# nunchuck_v0_4.net
KiCad netlist of a schematic drawn in EAGLE
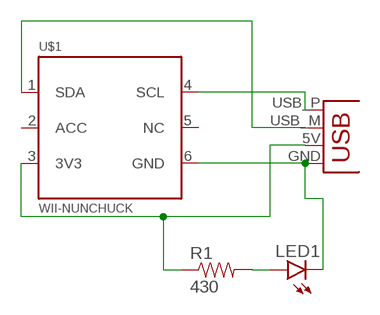
[diagram p0: schematic, sheet 1]

(export (version "E")
  (design (tool "Eeschema 10.0.6"))
  (components
    (comp (ref "JP1")
      (value "USBPCB")
      (footprint "eagle-import:USB-A-PCB")
      (libsource (lib "eagle-import") (part "USBPCB"))
    )
    (comp (ref "LED1")
      (value "LED0603")
      (footprint "eagle-import:LED-0603")
      (libsource (lib "eagle-import") (part "LED0603"))
    )
    (comp (ref "R1")
      (value "430")
      (footprint "eagle-import:0603-RES")
      (libsource (lib "eagle-import") (part "RESISTOR0603"))
    )
    (comp (ref "U$1")
      (value "WII-NUNCHUCK")
      (footprint "eagle-import:WII_6PIN")
      (libsource (lib "eagle-import") (part "WII-NUNCHUCK"))
    )
  )
  (nets
    (net (code "1") (name "Net-(JP1-D+)") (class "Default")
      (node (ref "JP1") (pin "USB_P") (pinfunction "D+_USB_P") (pintype "bidirectional"))
      (node (ref "U$1") (pin "4") (pinfunction "SCL_4") (pintype "bidirectional"))
    )
    (net (code "2") (name "Net-(JP1-D-)") (class "Default")
      (node (ref "JP1") (pin "USB_M") (pinfunction "D-_USB_M") (pintype "bidirectional"))
      (node (ref "U$1") (pin "1") (pinfunction "SDA_1") (pintype "bidirectional"))
    )
    (net (code "3") (name "Net-(JP1-VBUS)") (class "Default")
      (node (ref "JP1") (pin "5V") (pinfunction "VBUS_5V") (pintype "bidirectional"))
      (node (ref "R1") (pin "1") (pinfunction "1_1") (pintype "passive"))
      (node (ref "U$1") (pin "3") (pinfunction "3V3_3") (pintype "power_in"))
    )
    (net (code "4") (name "Net-(LED1-PadA)") (class "Default")
      (node (ref "LED1") (pin "A") (pinfunction "A_A") (pintype "passive"))
      (node (ref "R1") (pin "2") (pinfunction "2_2") (pintype "passive"))
    )
    (net (code "5") (name "Net-(U$1-GND)") (class "Default")
      (node (ref "JP1") (pin "GND") (pinfunction "GND_GND") (pintype "bidirectional"))
      (node (ref "LED1") (pin "C") (pinfunction "C_C") (pintype "passive"))
      (node (ref "U$1") (pin "6") (pinfunction "GND_6") (pintype "power_in"))
    )
    (net (code "6") (name "unconnected-(U$1-ACC-Pad2)") (class "Default")
      (node (ref "U$1") (pin "2") (pinfunction "ACC_2") (pintype "bidirectional"))
    )
    (net (code "7") (name "unconnected-(U$1-NC-Pad5)") (class "Default")
      (node (ref "U$1") (pin "5") (pinfunction "NC_5") (pintype "no_connect"))
    )
  )
)
